# C8.net
KiCad netlist of a schematic drawn in Altium Designer
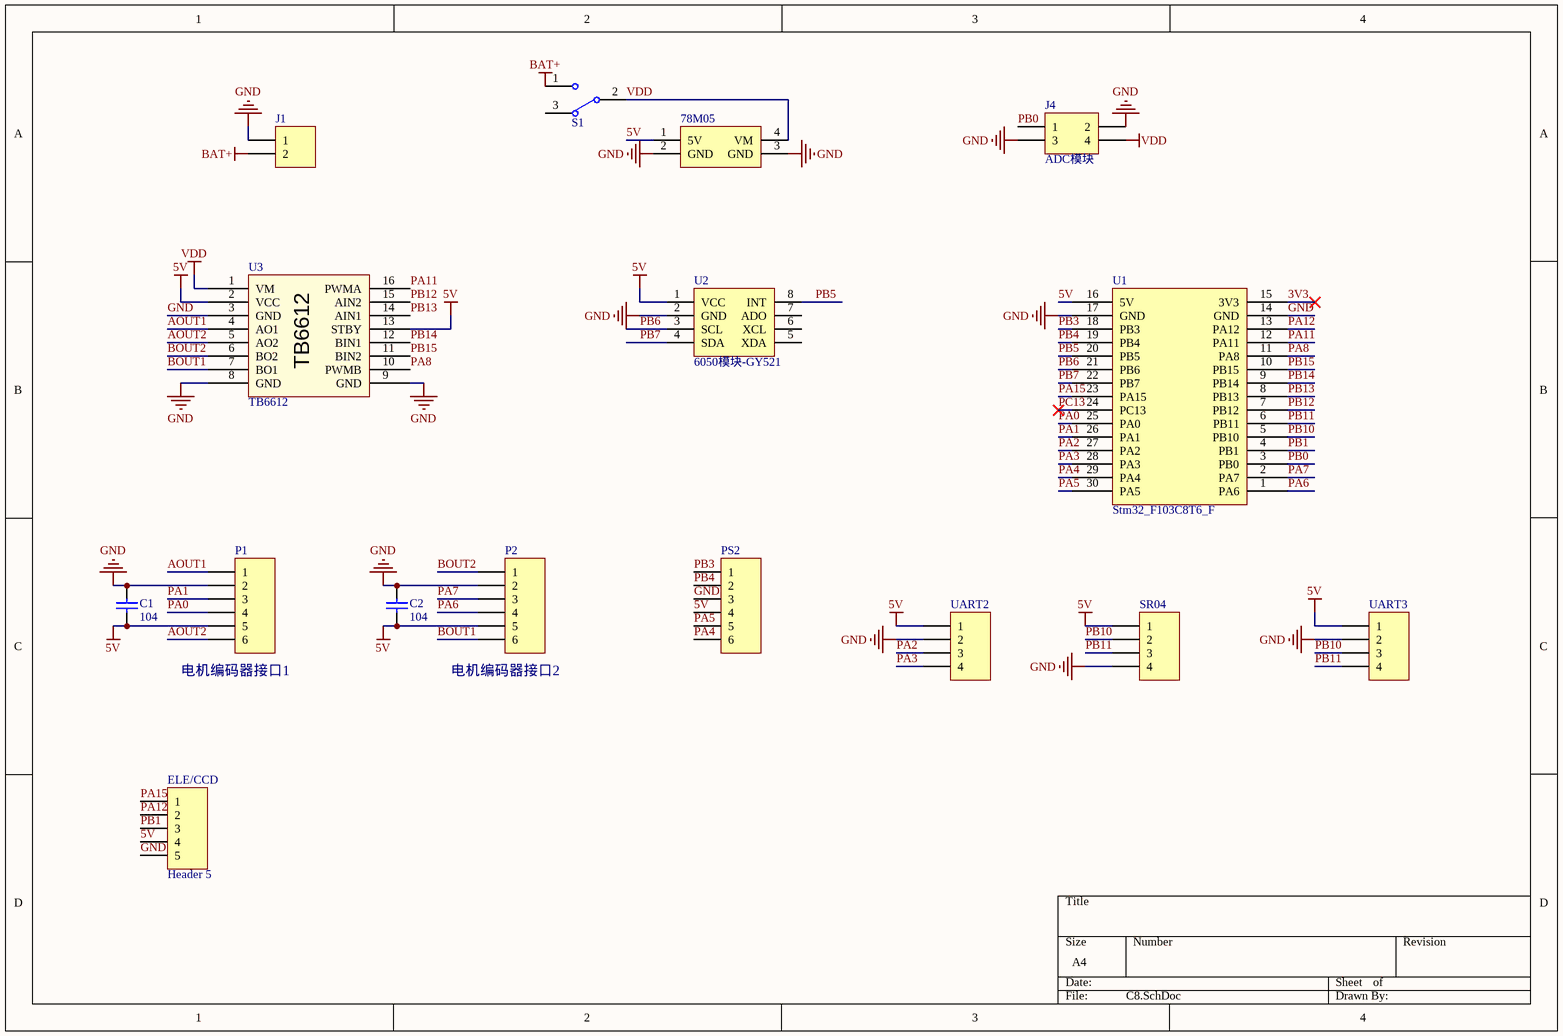
[diagram p0: C8.SchDoc]

(export (version "E")
  (design (tool "Eeschema 10.0.6"))
  (components
    (comp (ref "78M05") (value "78M05") (footprint "MP2259_M0") (libsource (lib "Model") (part "MP2259模块")))
    (comp (ref "C1")
      (value "104")
      (footprint "MLCC5.08-A")
      (description "Capacitor")
      (fields (field (name "PUBLISHER") "Altium Limited"))
      (libsource (lib "Miscellaneous Devices") (part "Cap"))
    )
    (comp (ref "C2")
      (value "104")
      (footprint "MLCC5.08-A")
      (description "Capacitor")
      (fields (field (name "PUBLISHER") "Altium Limited"))
      (libsource (lib "Miscellaneous Devices") (part "Cap"))
    )
    (comp (ref "ELE/CCD")
      (value "Header 5")
      (footprint "XH2.54-LI-5P")
      (description "Header, 5-Pin")
      (fields (field (name "PUBLISHER") "Altium Limited"))
      (libsource (lib "Miscellaneous Connectors") (part "Header 5"))
    )
    (comp (ref "J1")
      (value "Header 2")
      (footprint "XT30-PW-M")
      (description "Header, 2-Pin")
      (fields (field (name "PUBLISHER") "Altium Limited"))
      (libsource (lib "Miscellaneous Connectors") (part "Header 2"))
    )
    (comp (ref "J4")
      (value "ADC模块")
      (footprint "ADC_A0")
      (description "Header, 2-Pin, Dual row")
      (fields (field (name "PUBLISHER") "Altium Limited"))
      (libsource (lib "Miscellaneous Connectors") (part "Header 2X2"))
    )
    (comp (ref "P1")
      (value "Header 6")
      (footprint "XH2.54-WI-6P")
      (description "Header, 6-Pin")
      (fields (field (name "PUBLISHER") "Altium Limited"))
      (libsource (lib "Miscellaneous Connectors") (part "Header 6"))
    )
    (comp (ref "P2")
      (value "Header 6")
      (footprint "XH2.54-WI-6P")
      (description "Header, 6-Pin")
      (fields (field (name "PUBLISHER") "Altium Limited"))
      (libsource (lib "Miscellaneous Connectors") (part "Header 6"))
    )
    (comp (ref "PS2")
      (value "Header 6")
      (footprint "XH2.54-LI-6P")
      (description "Header, 6-Pin")
      (fields (field (name "PUBLISHER") "Altium Limited"))
      (libsource (lib "Miscellaneous Connectors") (part "Header 6"))
    )
    (comp (ref "S1")
      (value "SW-SPDT")
      (footprint "SW")
      (description "SPDT Subminiature Toggle Switch, Right Angle Mounting, Vertical Actuation")
      (fields (field (name "PUBLISHER") "Altium Limited"))
      (libsource (lib "Miscellaneous Devices") (part "SW-SPDT"))
    )
    (comp (ref "SR04")
      (value "Header 4")
      (footprint "HDR1X4")
      (description "Header, 4-Pin")
      (fields (field (name "PUBLISHER") "Altium Limited"))
      (libsource (lib "Miscellaneous Connectors") (part "Header 4"))
    )
    (comp (ref "U1")
      (value "Stm32_F103C8T6_F")
      (footprint "Stm32_F103C8T6_F")
      (libsource (lib "Model") (part "Stm32_F103C8T6_F"))
    )
    (comp (ref "U2")
      (value "6050模块-GY521")
      (footprint "MPU6050_B1")
      (libsource (lib "Model") (part "6050模块-GY521"))
    )
    (comp (ref "U3") (value "TB6612") (footprint "TB6612模块") (libsource (lib "DAYU") (part "DAYU_TB6612")))
    (comp (ref "UART2")
      (value "Header 4")
      (footprint "HDR1X4")
      (description "Header, 4-Pin")
      (fields (field (name "PUBLISHER") "Altium Limited"))
      (libsource (lib "Miscellaneous Connectors") (part "Header 4"))
    )
    (comp (ref "UART3")
      (value "Header 4")
      (footprint "HDR1X4")
      (description "Header, 4-Pin")
      (fields (field (name "PUBLISHER") "Altium Limited"))
      (libsource (lib "Miscellaneous Connectors") (part "Header 4"))
    )
  )
  (nets
    (net (code "1") (name "/3V3") (class "Default")
      (node (ref "U1") (pin "15") (pinfunction "3V3_15") (pintype "passive+no_connect"))
    )
    (net (code "2") (name "/AOUT1") (class "Default")
      (node (ref "P1") (pin "1") (pinfunction "1_1") (pintype "passive"))
      (node (ref "U3") (pin "4") (pinfunction "AO1_4") (pintype "passive"))
    )
    (net (code "3") (name "/AOUT2") (class "Default")
      (node (ref "P1") (pin "6") (pinfunction "6_6") (pintype "passive"))
      (node (ref "U3") (pin "5") (pinfunction "AO2_5") (pintype "passive"))
    )
    (net (code "4") (name "/BOUT1") (class "Default")
      (node (ref "P2") (pin "6") (pinfunction "6_6") (pintype "passive"))
      (node (ref "U3") (pin "7") (pinfunction "BO1_7") (pintype "passive"))
    )
    (net (code "5") (name "/BOUT2") (class "Default")
      (node (ref "P2") (pin "1") (pinfunction "1_1") (pintype "passive"))
      (node (ref "U3") (pin "6") (pinfunction "BO2_6") (pintype "passive"))
    )
    (net (code "6") (name "/PA0") (class "Default")
      (node (ref "P1") (pin "4") (pinfunction "4_4") (pintype "passive"))
      (node (ref "U1") (pin "25") (pinfunction "PA0_25") (pintype "passive"))
    )
    (net (code "7") (name "/PA1") (class "Default")
      (node (ref "P1") (pin "3") (pinfunction "3_3") (pintype "passive"))
      (node (ref "U1") (pin "26") (pinfunction "PA1_26") (pintype "passive"))
    )
    (net (code "8") (name "/PA2") (class "Default")
      (node (ref "U1") (pin "27") (pinfunction "PA2_27") (pintype "passive"))
      (node (ref "UART2") (pin "3") (pinfunction "3_3") (pintype "passive"))
    )
    (net (code "9") (name "/PA3") (class "Default")
      (node (ref "U1") (pin "28") (pinfunction "PA3_28") (pintype "passive"))
      (node (ref "UART2") (pin "4") (pinfunction "4_4") (pintype "passive"))
    )
    (net (code "10") (name "/PA4") (class "Default")
      (node (ref "PS2") (pin "6") (pinfunction "6_6") (pintype "passive"))
      (node (ref "U1") (pin "29") (pinfunction "PA4_29") (pintype "passive"))
    )
    (net (code "11") (name "/PA5") (class "Default")
      (node (ref "PS2") (pin "5") (pinfunction "5_5") (pintype "passive"))
      (node (ref "U1") (pin "30") (pinfunction "PA5_30") (pintype "passive"))
    )
    (net (code "12") (name "/PA6") (class "Default")
      (node (ref "P2") (pin "4") (pinfunction "4_4") (pintype "passive"))
      (node (ref "U1") (pin "1") (pinfunction "PA6_1") (pintype "passive"))
    )
    (net (code "13") (name "/PA7") (class "Default")
      (node (ref "P2") (pin "3") (pinfunction "3_3") (pintype "passive"))
      (node (ref "U1") (pin "2") (pinfunction "PA7_2") (pintype "passive"))
    )
    (net (code "14") (name "/PA8") (class "Default")
      (node (ref "U1") (pin "11") (pinfunction "PA8_11") (pintype "passive"))
      (node (ref "U3") (pin "10") (pinfunction "PWMB_10") (pintype "passive"))
    )
    (net (code "15") (name "/PA11") (class "Default")
      (node (ref "U1") (pin "12") (pinfunction "PA11_12") (pintype "passive"))
      (node (ref "U3") (pin "16") (pinfunction "PWMA_16") (pintype "passive"))
    )
    (net (code "16") (name "/PA12") (class "Default")
      (node (ref "ELE/CCD") (pin "2") (pinfunction "2_2") (pintype "passive"))
      (node (ref "U1") (pin "13") (pinfunction "PA12_13") (pintype "passive"))
    )
    (net (code "17") (name "/PA15") (class "Default")
      (node (ref "ELE/CCD") (pin "1") (pinfunction "1_1") (pintype "passive"))
      (node (ref "U1") (pin "23") (pinfunction "PA15_23") (pintype "passive"))
    )
    (net (code "18") (name "/PB0") (class "Default")
      (node (ref "J4") (pin "1") (pinfunction "1_1") (pintype "passive"))
      (node (ref "U1") (pin "3") (pinfunction "PB0_3") (pintype "passive"))
    )
    (net (code "19") (name "/PB1") (class "Default")
      (node (ref "ELE/CCD") (pin "3") (pinfunction "3_3") (pintype "passive"))
      (node (ref "U1") (pin "4") (pinfunction "PB1_4") (pintype "passive"))
    )
    (net (code "20") (name "/PB3") (class "Default")
      (node (ref "PS2") (pin "1") (pinfunction "1_1") (pintype "passive"))
      (node (ref "U1") (pin "18") (pinfunction "PB3_18") (pintype "passive"))
    )
    (net (code "21") (name "/PB4") (class "Default")
      (node (ref "PS2") (pin "2") (pinfunction "2_2") (pintype "passive"))
      (node (ref "U1") (pin "19") (pinfunction "PB4_19") (pintype "passive"))
    )
    (net (code "22") (name "/PB5") (class "Default")
      (node (ref "U1") (pin "20") (pinfunction "PB5_20") (pintype "passive"))
      (node (ref "U2") (pin "8") (pinfunction "INT_8") (pintype "passive"))
    )
    (net (code "23") (name "/PB6") (class "Default")
      (node (ref "U1") (pin "21") (pinfunction "PB6_21") (pintype "passive"))
      (node (ref "U2") (pin "3") (pinfunction "SCL_3") (pintype "passive"))
    )
    (net (code "24") (name "/PB7") (class "Default")
      (node (ref "U1") (pin "22") (pinfunction "PB7_22") (pintype "passive"))
      (node (ref "U2") (pin "4") (pinfunction "SDA_4") (pintype "passive"))
    )
    (net (code "25") (name "/PB10") (class "Default")
      (node (ref "SR04") (pin "2") (pinfunction "2_2") (pintype "passive"))
      (node (ref "U1") (pin "5") (pinfunction "PB10_5") (pintype "passive"))
      (node (ref "UART3") (pin "3") (pinfunction "3_3") (pintype "passive"))
    )
    (net (code "26") (name "/PB11") (class "Default")
      (node (ref "SR04") (pin "3") (pinfunction "3_3") (pintype "passive"))
      (node (ref "U1") (pin "6") (pinfunction "PB11_6") (pintype "passive"))
      (node (ref "UART3") (pin "4") (pinfunction "4_4") (pintype "passive"))
    )
    (net (code "27") (name "/PB12") (class "Default")
      (node (ref "U1") (pin "7") (pinfunction "PB12_7") (pintype "passive"))
      (node (ref "U3") (pin "15") (pinfunction "AIN2_15") (pintype "passive"))
    )
    (net (code "28") (name "/PB13") (class "Default")
      (node (ref "U1") (pin "8") (pinfunction "PB13_8") (pintype "passive"))
      (node (ref "U3") (pin "14") (pinfunction "AIN1_14") (pintype "passive"))
    )
    (net (code "29") (name "/PB14") (class "Default")
      (node (ref "U1") (pin "9") (pinfunction "PB14_9") (pintype "passive"))
      (node (ref "U3") (pin "12") (pinfunction "BIN1_12") (pintype "passive"))
    )
    (net (code "30") (name "/PB15") (class "Default")
      (node (ref "U1") (pin "10") (pinfunction "PB15_10") (pintype "passive"))
      (node (ref "U3") (pin "11") (pinfunction "BIN2_11") (pintype "passive"))
    )
    (net (code "31") (name "/PC13") (class "Default")
      (node (ref "U1") (pin "24") (pinfunction "PC13_24") (pintype "passive+no_connect"))
    )
    (net (code "32") (name "5V") (class "Default")
      (node (ref "78M05") (pin "1") (pinfunction "5V_1") (pintype "passive"))
      (node (ref "C1") (pin "1") (pinfunction "1_1") (pintype "passive"))
      (node (ref "C2") (pin "1") (pinfunction "1_1") (pintype "passive"))
      (node (ref "ELE/CCD") (pin "4") (pinfunction "4_4") (pintype "passive"))
      (node (ref "P1") (pin "5") (pinfunction "5_5") (pintype "passive"))
      (node (ref "P2") (pin "5") (pinfunction "5_5") (pintype "passive"))
      (node (ref "PS2") (pin "4") (pinfunction "4_4") (pintype "passive"))
      (node (ref "SR04") (pin "1") (pinfunction "1_1") (pintype "passive"))
      (node (ref "U1") (pin "16") (pinfunction "5V_16") (pintype "passive"))
      (node (ref "U2") (pin "1") (pinfunction "VCC_1") (pintype "passive"))
      (node (ref "U3") (pin "13") (pinfunction "STBY_13") (pintype "passive"))
      (node (ref "U3") (pin "2") (pinfunction "VCC_2") (pintype "passive"))
      (node (ref "UART2") (pin "1") (pinfunction "1_1") (pintype "passive"))
      (node (ref "UART3") (pin "1") (pinfunction "1_1") (pintype "passive"))
    )
    (net (code "33") (name "BAT+") (class "Default")
      (node (ref "J1") (pin "2") (pinfunction "2_2") (pintype "passive"))
      (node (ref "S1") (pin "1") (pinfunction "1_1") (pintype "passive"))
    )
    (net (code "34") (name "GND") (class "Default")
      (node (ref "78M05") (pin "2") (pinfunction "GND_2") (pintype "passive"))
      (node (ref "78M05") (pin "3") (pinfunction "GND_3") (pintype "passive"))
      (node (ref "C1") (pin "2") (pinfunction "2_2") (pintype "passive"))
      (node (ref "C2") (pin "2") (pinfunction "2_2") (pintype "passive"))
      (node (ref "ELE/CCD") (pin "5") (pinfunction "5_5") (pintype "passive"))
      (node (ref "J1") (pin "1") (pinfunction "1_1") (pintype "passive"))
      (node (ref "J4") (pin "2") (pinfunction "2_2") (pintype "passive"))
      (node (ref "J4") (pin "3") (pinfunction "3_3") (pintype "passive"))
      (node (ref "P1") (pin "2") (pinfunction "2_2") (pintype "passive"))
      (node (ref "P2") (pin "2") (pinfunction "2_2") (pintype "passive"))
      (node (ref "PS2") (pin "3") (pinfunction "3_3") (pintype "passive"))
      (node (ref "SR04") (pin "4") (pinfunction "4_4") (pintype "passive"))
      (node (ref "U1") (pin "14") (pinfunction "GND_14") (pintype "passive"))
      (node (ref "U1") (pin "17") (pinfunction "GND_17") (pintype "passive"))
      (node (ref "U2") (pin "2") (pinfunction "GND_2") (pintype "passive"))
      (node (ref "U3") (pin "3") (pinfunction "GND_3") (pintype "passive"))
      (node (ref "U3") (pin "8") (pinfunction "GND_8") (pintype "passive"))
      (node (ref "U3") (pin "9") (pinfunction "GND_9") (pintype "passive"))
      (node (ref "UART2") (pin "2") (pinfunction "2_2") (pintype "passive"))
      (node (ref "UART3") (pin "2") (pinfunction "2_2") (pintype "passive"))
    )
    (net (code "35") (name "VDD") (class "Default")
      (node (ref "78M05") (pin "4") (pinfunction "VM_4") (pintype "passive"))
      (node (ref "J4") (pin "4") (pinfunction "4_4") (pintype "passive"))
      (node (ref "S1") (pin "2") (pinfunction "2_2") (pintype "passive"))
      (node (ref "U3") (pin "1") (pinfunction "VM_1") (pintype "passive"))
    )
    (net (code "36") (name "unconnected-(S1-Pad3)") (class "Default")
      (node (ref "S1") (pin "3") (pinfunction "3_3") (pintype "passive"))
    )
    (net (code "37") (name "unconnected-(U2-ADO-Pad7)") (class "Default")
      (node (ref "U2") (pin "7") (pinfunction "ADO_7") (pintype "passive"))
    )
    (net (code "38") (name "unconnected-(U2-XCL-Pad6)") (class "Default")
      (node (ref "U2") (pin "6") (pinfunction "XCL_6") (pintype "passive"))
    )
    (net (code "39") (name "unconnected-(U2-XDA-Pad5)") (class "Default")
      (node (ref "U2") (pin "5") (pinfunction "XDA_5") (pintype "passive"))
    )
  )
)
